# module.net
KiCad netlist of a schematic drawn in EAGLE
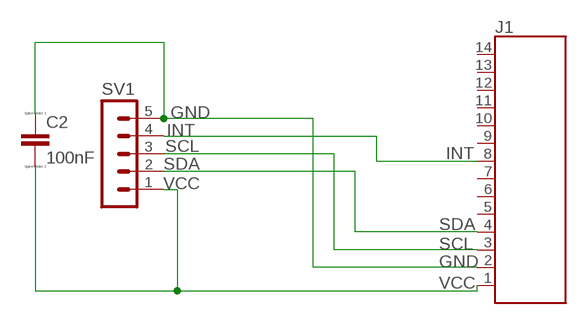
[diagram p0: schematic, sheet 1]

(export (version "E")
  (design (tool "Eeschema 10.0.6"))
  (components
    (comp (ref "C2")
      (value "100nF")
      (footprint "eagle-import:C1206")
      (libsource (lib "eagle-import") (part "CC1206"))
    )
    (comp (ref "J1")
      (value "686114183522")
      (footprint "eagle-import:686114183522")
      (libsource (lib "eagle-import") (part "686114183522"))
    )
    (comp (ref "SV1")
      (value "MA05-1")
      (footprint "eagle-import:MA05-1")
      (libsource (lib "eagle-import") (part "MA05-1"))
    )
  )
  (nets
    (net (code "1") (name "/GND") (class "Default")
      (node (ref "C2") (pin "1") (pinfunction "1_1") (pintype "passive"))
      (node (ref "J1") (pin "2") (pinfunction "13_2") (pintype "passive"))
      (node (ref "SV1") (pin "5") (pinfunction "5_5") (pintype "passive"))
    )
    (net (code "2") (name "/INT") (class "Default")
      (node (ref "J1") (pin "8") (pinfunction "7_8") (pintype "passive"))
      (node (ref "SV1") (pin "4") (pinfunction "4_4") (pintype "passive"))
    )
    (net (code "3") (name "/SCL") (class "Default")
      (node (ref "J1") (pin "3") (pinfunction "12_3") (pintype "passive"))
      (node (ref "SV1") (pin "3") (pinfunction "3_3") (pintype "passive"))
    )
    (net (code "4") (name "/SDA") (class "Default")
      (node (ref "J1") (pin "4") (pinfunction "11_4") (pintype "passive"))
      (node (ref "SV1") (pin "2") (pinfunction "2_2") (pintype "passive"))
    )
    (net (code "5") (name "/VCC") (class "Default")
      (node (ref "C2") (pin "2") (pinfunction "2_2") (pintype "passive"))
      (node (ref "J1") (pin "1") (pinfunction "14_1") (pintype "passive"))
      (node (ref "SV1") (pin "1") (pinfunction "1_1") (pintype "passive"))
    )
    (net (code "6") (name "unconnected-(J1-1-Pad14)") (class "Default")
      (node (ref "J1") (pin "14") (pinfunction "1_14") (pintype "passive"))
    )
    (net (code "7") (name "unconnected-(J1-2-Pad13)") (class "Default")
      (node (ref "J1") (pin "13") (pinfunction "2_13") (pintype "passive"))
    )
    (net (code "8") (name "unconnected-(J1-3-Pad12)") (class "Default")
      (node (ref "J1") (pin "12") (pinfunction "3_12") (pintype "passive"))
    )
    (net (code "9") (name "unconnected-(J1-4-Pad11)") (class "Default")
      (node (ref "J1") (pin "11") (pinfunction "4_11") (pintype "passive"))
    )
    (net (code "10") (name "unconnected-(J1-5-Pad10)") (class "Default")
      (node (ref "J1") (pin "10") (pinfunction "5_10") (pintype "passive"))
    )
    (net (code "11") (name "unconnected-(J1-6-Pad9)") (class "Default")
      (node (ref "J1") (pin "9") (pinfunction "6_9") (pintype "passive"))
    )
    (net (code "12") (name "unconnected-(J1-8-Pad7)") (class "Default")
      (node (ref "J1") (pin "7") (pinfunction "8_7") (pintype "passive"))
    )
    (net (code "13") (name "unconnected-(J1-9-Pad6)") (class "Default")
      (node (ref "J1") (pin "6") (pinfunction "9_6") (pintype "passive"))
    )
    (net (code "14") (name "unconnected-(J1-10-Pad5)") (class "Default")
      (node (ref "J1") (pin "5") (pinfunction "10_5") (pintype "passive"))
    )
  )
)
